# LocoShield.net
KiCad netlist of a schematic drawn in EAGLE
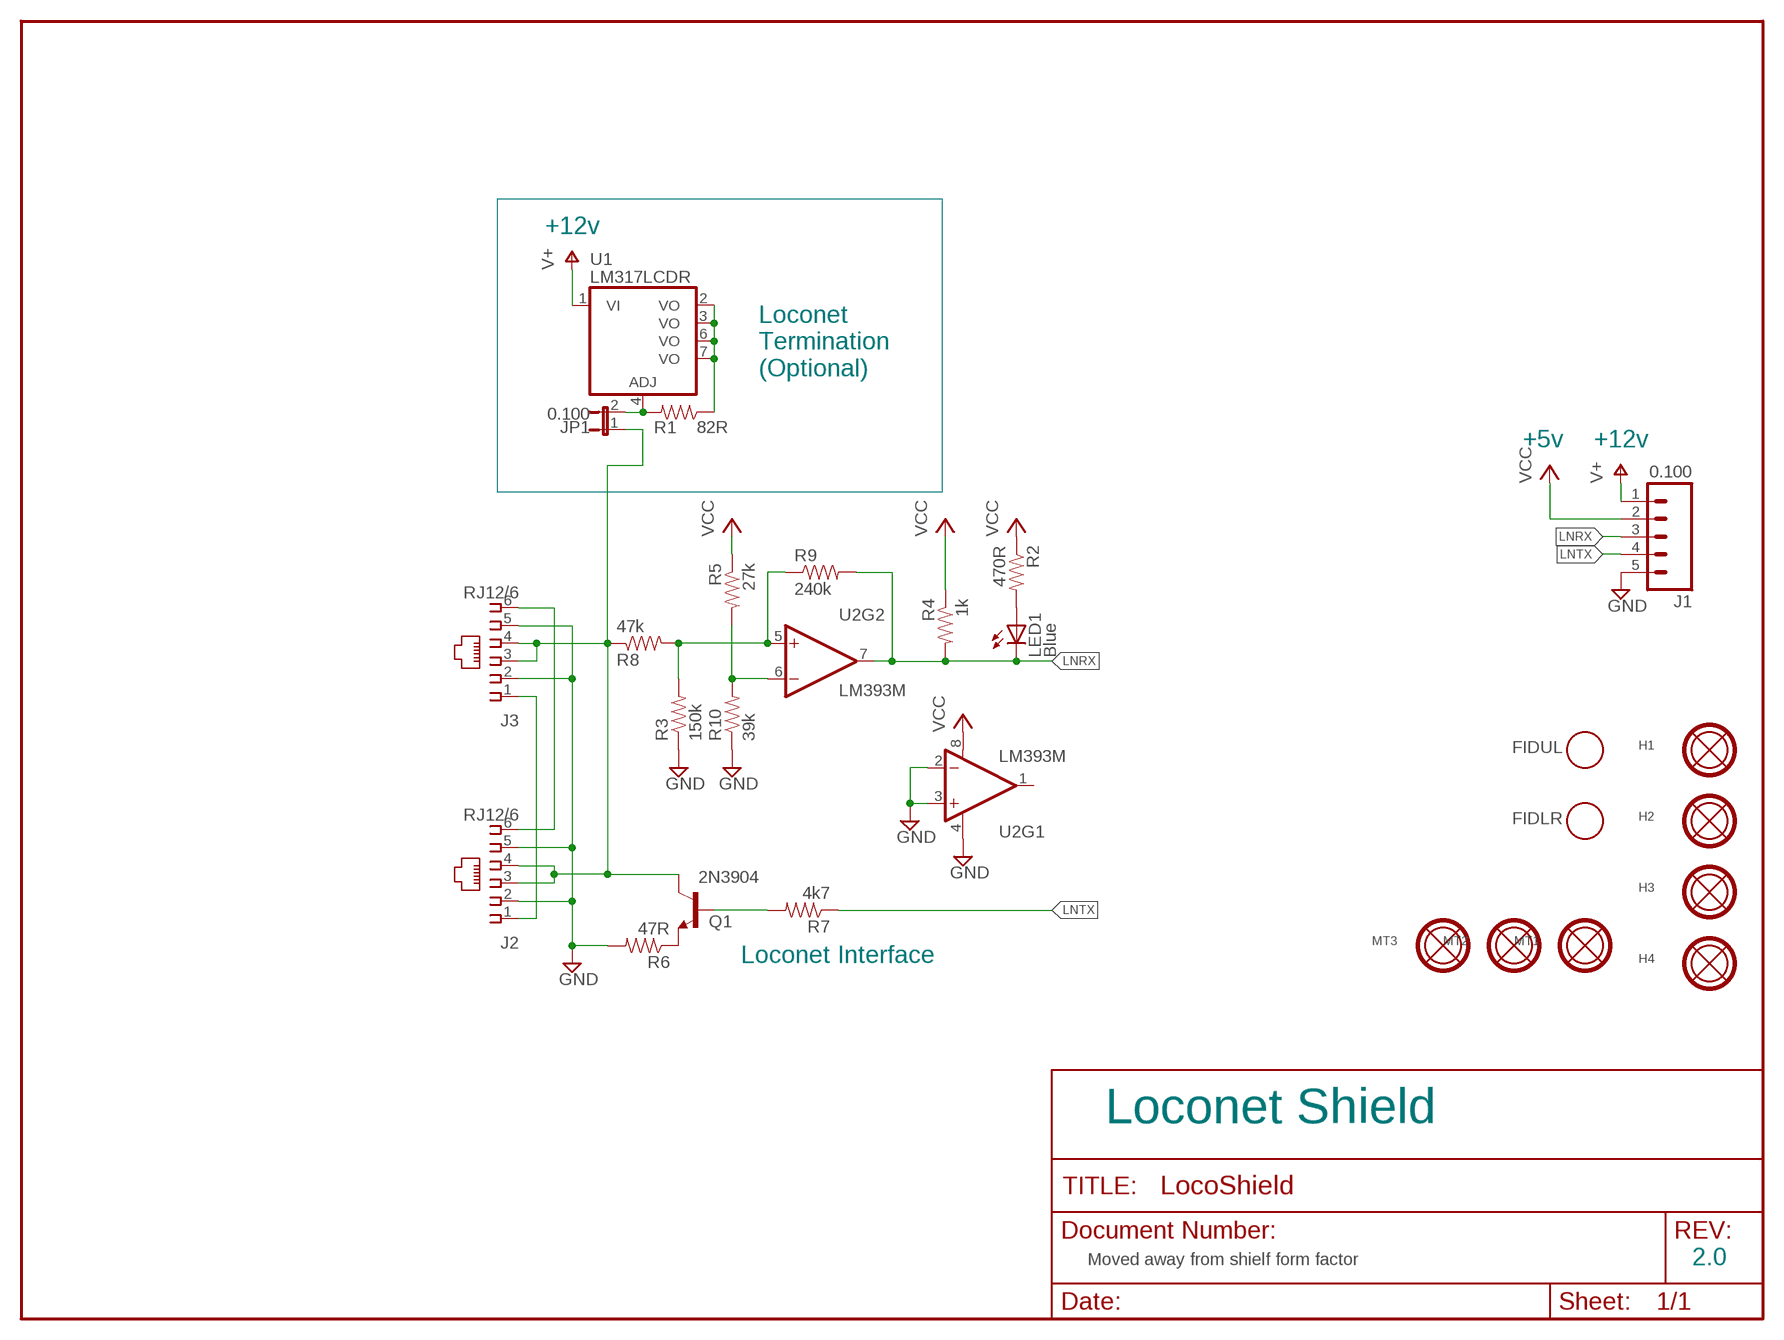
[diagram p0: schematic, sheet 1]

(export (version "E")
  (design (tool "Eeschema 10.0.6"))
  (components
    (comp (ref "FIDLR")
      (value "FIDUCIAL")
      (footprint "eagle-import:FIDUCIAL_1MM")
      (libsource (lib "eagle-import") (part "FIDUCIAL"))
    )
    (comp (ref "FIDUL")
      (value "FIDUCIAL")
      (footprint "eagle-import:FIDUCIAL_1MM")
      (libsource (lib "eagle-import") (part "FIDUCIAL"))
    )
    (comp (ref "H1")
      (value "MOUNTINGHOLEL")
      (footprint "eagle-import:MOUNTINGHOLE-L")
      (libsource (lib "eagle-import") (part "MOUNTINGHOLEL"))
    )
    (comp (ref "H2")
      (value "MOUNTINGHOLEL")
      (footprint "eagle-import:MOUNTINGHOLE-L")
      (libsource (lib "eagle-import") (part "MOUNTINGHOLEL"))
    )
    (comp (ref "H3")
      (value "MOUNTINGHOLEL")
      (footprint "eagle-import:MOUNTINGHOLE-L")
      (libsource (lib "eagle-import") (part "MOUNTINGHOLEL"))
    )
    (comp (ref "H4")
      (value "MOUNTINGHOLEL")
      (footprint "eagle-import:MOUNTINGHOLE-L")
      (libsource (lib "eagle-import") (part "MOUNTINGHOLEL"))
    )
    (comp (ref "J1")
      (value "0.100")
      (footprint "eagle-import:1X05_LOCK")
      (libsource (lib "eagle-import") (part "CONNECTOR-M05LOCK"))
    )
    (comp (ref "J2")
      (value "RJ12/6")
      (footprint "eagle-import:RJ25-PANEL")
      (libsource (lib "eagle-import") (part "CONNECTOR-RJ25-6P6C"))
    )
    (comp (ref "J3")
      (value "RJ12/6")
      (footprint "eagle-import:RJ25-PANEL")
      (libsource (lib "eagle-import") (part "CONNECTOR-RJ25-6P6C"))
    )
    (comp (ref "JP1")
      (value "0.100")
      (footprint "eagle-import:1X02_LOCK")
      (libsource (lib "eagle-import") (part "JUMPER-2PTH_LOCK"))
    )
    (comp (ref "LED1")
      (value "Blue")
      (footprint "eagle-import:0603-LED")
      (libsource (lib "eagle-import") (part "LED0603-LED"))
    )
    (comp (ref "MT1")
      (value "tool")
      (footprint "eagle-import:MOUNTINGHOLE-TOOL")
      (libsource (lib "eagle-import") (part "MOUNTINGHOLET"))
    )
    (comp (ref "MT2")
      (value "tool")
      (footprint "eagle-import:MOUNTINGHOLE-TOOL")
      (libsource (lib "eagle-import") (part "MOUNTINGHOLET"))
    )
    (comp (ref "MT3")
      (value "tool")
      (footprint "eagle-import:MOUNTINGHOLE-TOOL")
      (libsource (lib "eagle-import") (part "MOUNTINGHOLET"))
    )
    (comp (ref "Q1")
      (value "2N3904")
      (footprint "eagle-import:SOT23")
      (libsource (lib "eagle-import") (part "NPN-SOT23"))
    )
    (comp (ref "R1")
      (value "82R")
      (footprint "eagle-import:0603-RES")
      (libsource (lib "eagle-import") (part "R0603-RES"))
    )
    (comp (ref "R2")
      (value "470R")
      (footprint "eagle-import:0603-RES")
      (libsource (lib "eagle-import") (part "R0603-RES"))
    )
    (comp (ref "R3")
      (value "150k")
      (footprint "eagle-import:0603-RES")
      (libsource (lib "eagle-import") (part "R0603-RES"))
    )
    (comp (ref "R4")
      (value "1k")
      (footprint "eagle-import:0603-RES")
      (libsource (lib "eagle-import") (part "R0603-RES"))
    )
    (comp (ref "R5")
      (value "27k")
      (footprint "eagle-import:0603-RES")
      (libsource (lib "eagle-import") (part "R0603-RES"))
    )
    (comp (ref "R6")
      (value "47R")
      (footprint "eagle-import:0603-RES")
      (libsource (lib "eagle-import") (part "R0603-RES"))
    )
    (comp (ref "R7")
      (value "4k7")
      (footprint "eagle-import:0603-RES")
      (libsource (lib "eagle-import") (part "R0603-RES"))
    )
    (comp (ref "R8")
      (value "47k")
      (footprint "eagle-import:0603-RES")
      (libsource (lib "eagle-import") (part "R0603-RES"))
    )
    (comp (ref "R9")
      (value "240k")
      (footprint "eagle-import:0603-RES")
      (libsource (lib "eagle-import") (part "R0603-RES"))
    )
    (comp (ref "R10")
      (value "39k")
      (footprint "eagle-import:0603-RES")
      (libsource (lib "eagle-import") (part "R0603-RES"))
    )
    (comp (ref "U1")
      (value "LM317LCDR")
      (footprint "eagle-import:SO08")
      (libsource (lib "eagle-import") (part "LM317LD"))
    )
    (comp (ref "U2")
      (value "LM393M")
      (footprint "eagle-import:SO08")
      (libsource (lib "eagle-import") (part "LM393M"))
    )
  )
  (nets
    (net (code "1") (name "GND") (class "Default")
      (node (ref "J1") (pin "5") (pinfunction "5_5") (pintype "passive"))
      (node (ref "J2") (pin "2") (pinfunction "2_2") (pintype "passive"))
      (node (ref "J2") (pin "5") (pinfunction "5_5") (pintype "passive"))
      (node (ref "J3") (pin "2") (pinfunction "2_2") (pintype "passive"))
      (node (ref "J3") (pin "5") (pinfunction "5_5") (pintype "passive"))
      (node (ref "R10") (pin "1") (pinfunction "1_1") (pintype "passive"))
      (node (ref "R3") (pin "1") (pinfunction "1_1") (pintype "passive"))
      (node (ref "R6") (pin "2") (pinfunction "2_2") (pintype "passive"))
      (node (ref "U2") (pin "2") (pinfunction "-IN_2") (pintype "input"))
      (node (ref "U2") (pin "3") (pinfunction "+IN_3") (pintype "input"))
      (node (ref "U2") (pin "4") (pinfunction "V-_4") (pintype "power_in"))
    )
    (net (code "2") (name "LNRX") (class "Default")
      (node (ref "J1") (pin "3") (pinfunction "3_3") (pintype "passive"))
      (node (ref "LED1") (pin "C") (pinfunction "C_C") (pintype "passive"))
      (node (ref "R4") (pin "2") (pinfunction "2_2") (pintype "passive"))
      (node (ref "R9") (pin "2") (pinfunction "2_2") (pintype "passive"))
      (node (ref "U2") (pin "7") (pinfunction "OUT_7") (pintype "output"))
    )
    (net (code "3") (name "LNTX") (class "Default")
      (node (ref "J1") (pin "4") (pinfunction "4_4") (pintype "passive"))
      (node (ref "R7") (pin "1") (pinfunction "1_1") (pintype "passive"))
    )
    (net (code "4") (name "Net-(J2-Pad1)") (class "Default")
      (node (ref "J2") (pin "1") (pinfunction "1_1") (pintype "passive"))
      (node (ref "J3") (pin "1") (pinfunction "1_1") (pintype "passive"))
    )
    (net (code "5") (name "Net-(J2-Pad6)") (class "Default")
      (node (ref "J2") (pin "6") (pinfunction "6_6") (pintype "passive"))
      (node (ref "J3") (pin "6") (pinfunction "6_6") (pintype "passive"))
    )
    (net (code "6") (name "Net-(LED1-PadA)") (class "Default")
      (node (ref "LED1") (pin "A") (pinfunction "A_A") (pintype "passive"))
      (node (ref "R2") (pin "2") (pinfunction "2_2") (pintype "passive"))
    )
    (net (code "7") (name "Net-(Q1-B)") (class "Default")
      (node (ref "Q1") (pin "1") (pinfunction "B_1") (pintype "passive"))
      (node (ref "R7") (pin "2") (pinfunction "2_2") (pintype "passive"))
    )
    (net (code "8") (name "Net-(Q1-C)") (class "Default")
      (node (ref "J2") (pin "3") (pinfunction "3_3") (pintype "passive"))
      (node (ref "J2") (pin "4") (pinfunction "4_4") (pintype "passive"))
      (node (ref "J3") (pin "3") (pinfunction "3_3") (pintype "passive"))
      (node (ref "J3") (pin "4") (pinfunction "4_4") (pintype "passive"))
      (node (ref "JP1") (pin "1") (pinfunction "1_1") (pintype "passive"))
      (node (ref "Q1") (pin "3") (pinfunction "C_3") (pintype "passive"))
      (node (ref "R8") (pin "1") (pinfunction "1_1") (pintype "passive"))
    )
    (net (code "9") (name "Net-(Q1-E)") (class "Default")
      (node (ref "Q1") (pin "2") (pinfunction "E_2") (pintype "passive"))
      (node (ref "R6") (pin "1") (pinfunction "1_1") (pintype "passive"))
    )
    (net (code "10") (name "Net-(R1-Pad1)") (class "Default")
      (node (ref "R1") (pin "1") (pinfunction "1_1") (pintype "passive"))
      (node (ref "U1") (pin "2") (pinfunction "VO_2") (pintype "passive"))
      (node (ref "U1") (pin "3") (pinfunction "VO_3") (pintype "passive"))
      (node (ref "U1") (pin "6") (pinfunction "VO_6") (pintype "passive"))
      (node (ref "U1") (pin "7") (pinfunction "VO_7") (pintype "passive"))
    )
    (net (code "11") (name "Net-(U1-ADJ)") (class "Default")
      (node (ref "JP1") (pin "2") (pinfunction "2_2") (pintype "passive"))
      (node (ref "R1") (pin "2") (pinfunction "2_2") (pintype "passive"))
      (node (ref "U1") (pin "4") (pinfunction "ADJ_4") (pintype "input"))
    )
    (net (code "12") (name "Net-(U2B-+IN)") (class "Default")
      (node (ref "R3") (pin "2") (pinfunction "2_2") (pintype "passive"))
      (node (ref "R8") (pin "2") (pinfunction "2_2") (pintype "passive"))
      (node (ref "R9") (pin "1") (pinfunction "1_1") (pintype "passive"))
      (node (ref "U2") (pin "5") (pinfunction "+IN_5") (pintype "input"))
    )
    (net (code "13") (name "Net-(U2B--IN)") (class "Default")
      (node (ref "R10") (pin "2") (pinfunction "2_2") (pintype "passive"))
      (node (ref "R5") (pin "2") (pinfunction "2_2") (pintype "passive"))
      (node (ref "U2") (pin "6") (pinfunction "-IN_6") (pintype "input"))
    )
    (net (code "14") (name "V+") (class "Default")
      (node (ref "J1") (pin "1") (pinfunction "1_1") (pintype "passive"))
      (node (ref "U1") (pin "1") (pinfunction "VI_1") (pintype "input"))
    )
    (net (code "15") (name "VCC") (class "Default")
      (node (ref "J1") (pin "2") (pinfunction "2_2") (pintype "passive"))
      (node (ref "R2") (pin "1") (pinfunction "1_1") (pintype "passive"))
      (node (ref "R4") (pin "1") (pinfunction "1_1") (pintype "passive"))
      (node (ref "R5") (pin "1") (pinfunction "1_1") (pintype "passive"))
      (node (ref "U2") (pin "8") (pinfunction "V+_8") (pintype "power_in"))
    )
    (net (code "16") (name "unconnected-(U2A-OUT-Pad1)") (class "Default")
      (node (ref "U2") (pin "1") (pinfunction "OUT_1") (pintype "output"))
    )
  )
)
